# pilar_3_2_vers.net
KiCad netlist of a schematic drawn in Altium Designer
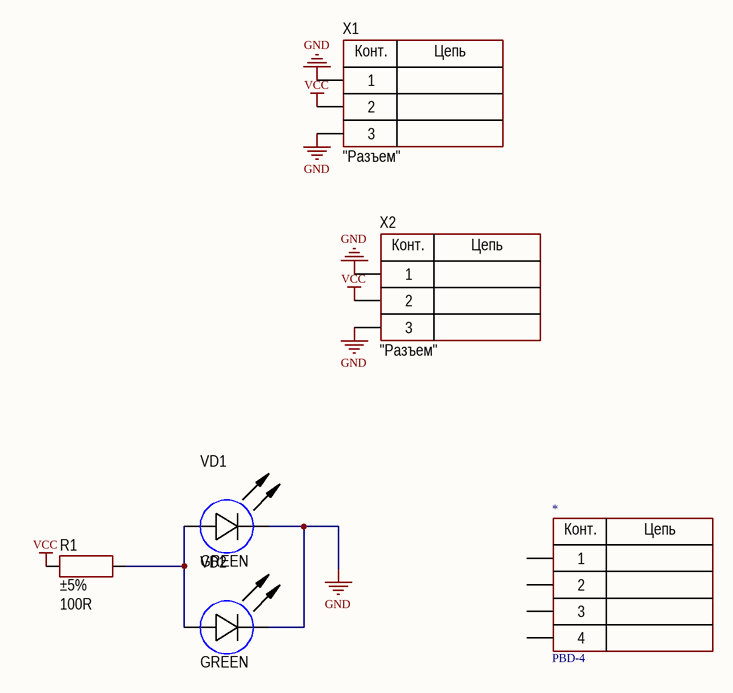
[diagram p0: pilar_3_2 vers.SchDoc]

(export (version "E")
  (design (tool "Eeschema 10.0.6"))
  (components
    (comp (ref "*") (value "PBD-4") (footprint "PLD-4-R") (libsource (lib "Connector") (part "PBD-4")))
    (comp (ref "R1")
      (value "100R")
      (footprint "RES: 0603")
      (fields
        (field (name "MANUFACTURER") "Yageo")
        (field (name "PARTNUMBER") "RC0603JR-07100RL")
        (field (name "VALUEMANUFACTURERPARTNUMBER") "Resistor film, 100R, ±5%, 0603, 0.1W, -55...+125°C")
        (field (name "TOLERANCE") "±5%")
      )
      (libsource (lib "Resistor") (part "Resistor_0603"))
    )
    (comp (ref "VD1")
      (value "~")
      (footprint "LED: 0805R")
      (fields
        (field (name "VALUEMANUFACTURERPARTNUMBER") "LED, *, *, *, -55...+150°C")
        (field (name "COLOR") "GREEN")
      )
      (libsource (lib "Diode") (part "LED_single"))
    )
    (comp (ref "VD2")
      (value "~")
      (footprint "LED: 0805R")
      (fields
        (field (name "VALUEMANUFACTURERPARTNUMBER") "LED, *, *, *, -55...+150°C")
        (field (name "COLOR") "GREEN")
      )
      (libsource (lib "Diode") (part "LED_single"))
    )
    (comp (ref "X1")
      (value "~")
      (footprint "CON: PLS-3")
      (fields
        (field (name "MANUFACTURER") "Connfly")
        (field (name "VALUEMANUFACTURERPARTNUMBER") "Connector, 3pin, 2.54mm, 500VAC, 3A")
        (field (name "PARTNUMBER") "PLS-3")
        (field (name "COMMENTTEXT") "\"Разъем\"")
      )
      (libsource (lib "Connector") (part "PLS-3"))
    )
    (comp (ref "X2")
      (value "~")
      (footprint "CON: PLS-3")
      (fields
        (field (name "MANUFACTURER") "Connfly")
        (field (name "VALUEMANUFACTURERPARTNUMBER") "Connector, 3pin, 2.54mm, 500VAC, 3A")
        (field (name "PARTNUMBER") "PLS-3")
        (field (name "COMMENTTEXT") "\"Разъем\"")
      )
      (libsource (lib "Connector") (part "PLS-3"))
    )
  )
  (nets
    (net (code "1") (name "GND") (class "Default")
      (node (ref "VD1") (pin "2") (pinfunction "C_2") (pintype "passive"))
      (node (ref "VD2") (pin "2") (pinfunction "C_2") (pintype "passive"))
      (node (ref "X1") (pin "1") (pinfunction "1_1") (pintype "passive"))
      (node (ref "X1") (pin "3") (pinfunction "3_3") (pintype "power_in"))
      (node (ref "X2") (pin "1") (pinfunction "1_1") (pintype "passive"))
      (node (ref "X2") (pin "3") (pinfunction "3_3") (pintype "power_in"))
    )
    (net (code "2") (name "Net-(VD1-A)") (class "Default")
      (node (ref "R1") (pin "2") (pinfunction "2_2") (pintype "passive"))
      (node (ref "VD1") (pin "1") (pinfunction "A_1") (pintype "passive"))
      (node (ref "VD2") (pin "1") (pinfunction "A_1") (pintype "passive"))
    )
    (net (code "3") (name "VCC") (class "Default")
      (node (ref "R1") (pin "1") (pinfunction "1_1") (pintype "passive"))
      (node (ref "X1") (pin "2") (pinfunction "2_2") (pintype "passive"))
      (node (ref "X2") (pin "2") (pinfunction "2_2") (pintype "passive"))
    )
    (net (code "4") (name "unconnected-(*-Pad1)") (class "Default")
      (node (ref "*") (pin "1") (pinfunction "1_1") (pintype "passive"))
    )
    (net (code "5") (name "unconnected-(*-Pad2)") (class "Default")
      (node (ref "*") (pin "2") (pinfunction "2_2") (pintype "passive"))
    )
    (net (code "6") (name "unconnected-(*-Pad3)") (class "Default")
      (node (ref "*") (pin "3") (pinfunction "3_3") (pintype "power_in"))
    )
    (net (code "7") (name "unconnected-(*-Pad4)") (class "Default")
      (node (ref "*") (pin "4") (pinfunction "4_4") (pintype "power_in"))
    )
  )
)
